# Sheet_4.net
KiCad netlist of a schematic drawn in Altium Designer
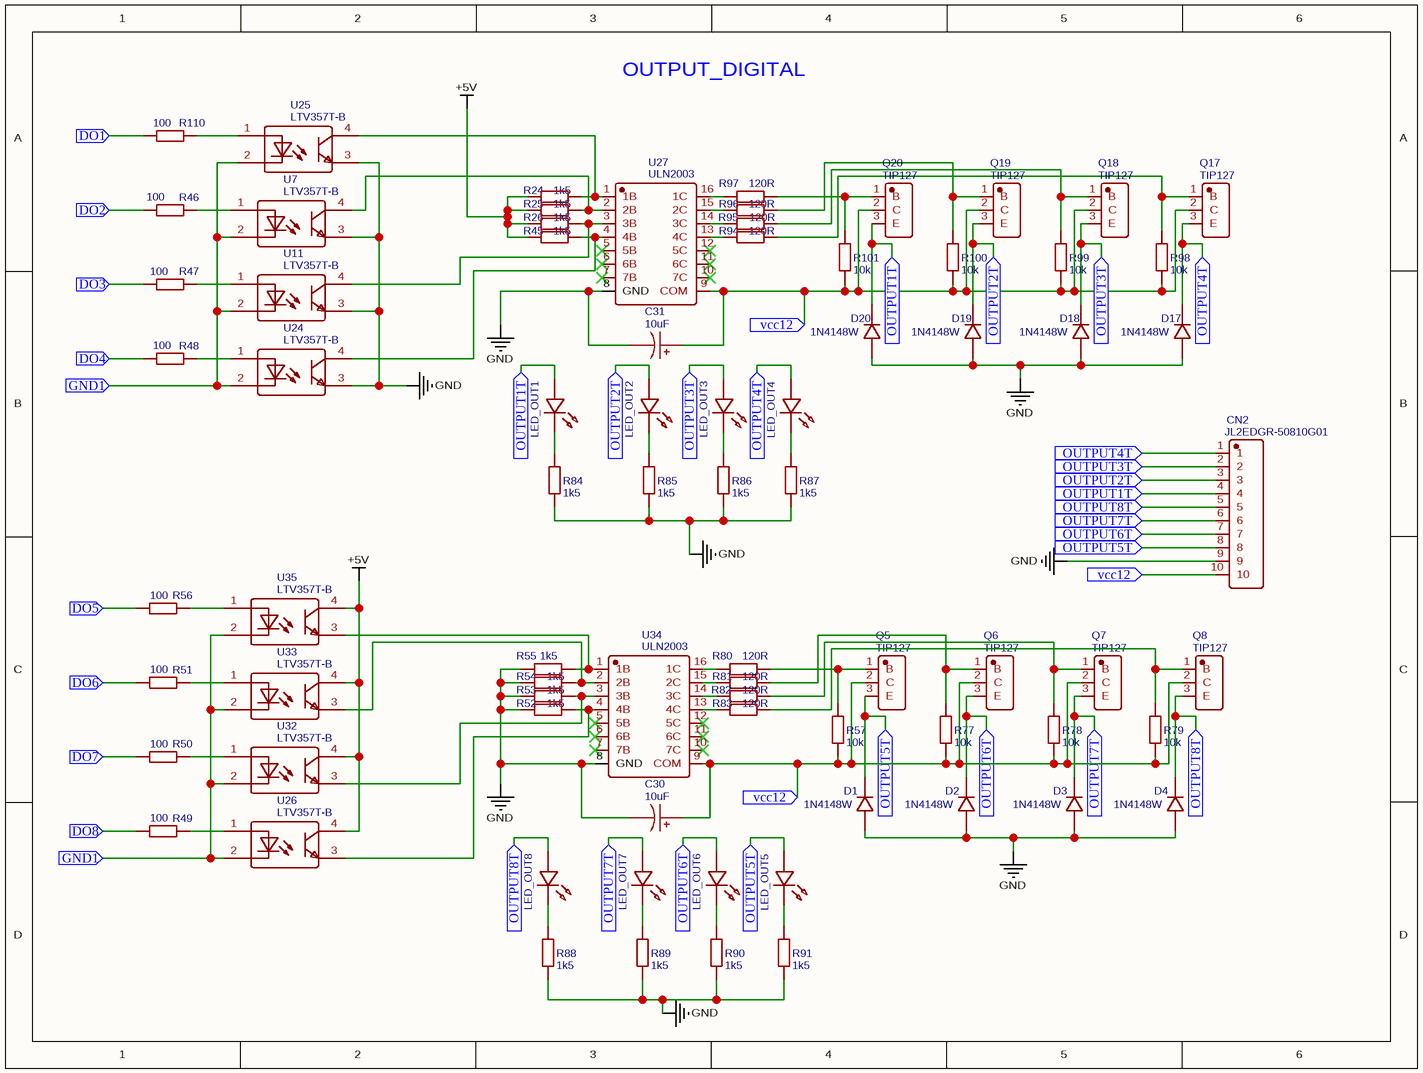
[diagram p0: Sheet_4.schdoc]

(export (version "E")
  (design (tool "Eeschema 10.0.6"))
  (components
    (comp (ref "C30")
      (value "10uF")
      (fields
        (field (name "BOM_SUPPLIER PART") "C503219")
        (field (name "BOM_MANUFACTURER PART") "01EC1809SHC10UF50V")
        (field (name "CONTRIBUTOR") "LCSC")
      )
      (libsource (lib "altium-import") (part "root_2_10uF_"))
    )
    (comp (ref "C31")
      (value "10uF")
      (fields
        (field (name "BOM_SUPPLIER PART") "C503219")
        (field (name "BOM_MANUFACTURER PART") "01EC1809SHC10UF50V")
        (field (name "CONTRIBUTOR") "LCSC")
      )
      (libsource (lib "altium-import") (part "root_2_10uF_"))
    )
    (comp (ref "CN2")
      (value "JL2EDGR-50810G01")
      (fields (field (name "BOM_SUPPLIER PART") "C424394") (field (name "CONTRIBUTOR") "LCSC"))
      (libsource (lib "altium-import") (part "root_0_JL2EDGR-50810G01_"))
    )
    (comp (ref "D1")
      (value "1N4148W")
      (fields (field (name "BOM_SUPPLIER PART") "C305437") (field (name "CONTRIBUTOR") "LCSC"))
      (libsource (lib "altium-import") (part "root_3_1N4148W_"))
    )
    (comp (ref "D2")
      (value "1N4148W")
      (fields (field (name "BOM_SUPPLIER PART") "C305437") (field (name "CONTRIBUTOR") "LCSC"))
      (libsource (lib "altium-import") (part "root_3_1N4148W_"))
    )
    (comp (ref "D3")
      (value "1N4148W")
      (fields (field (name "BOM_SUPPLIER PART") "C305437") (field (name "CONTRIBUTOR") "LCSC"))
      (libsource (lib "altium-import") (part "root_3_1N4148W_"))
    )
    (comp (ref "D4")
      (value "1N4148W")
      (fields (field (name "BOM_SUPPLIER PART") "C305437") (field (name "CONTRIBUTOR") "LCSC"))
      (libsource (lib "altium-import") (part "root_3_1N4148W_"))
    )
    (comp (ref "D17")
      (value "1N4148W")
      (fields (field (name "BOM_SUPPLIER PART") "C305437") (field (name "CONTRIBUTOR") "LCSC"))
      (libsource (lib "altium-import") (part "root_3_1N4148W_"))
    )
    (comp (ref "D18")
      (value "1N4148W")
      (fields (field (name "BOM_SUPPLIER PART") "C305437") (field (name "CONTRIBUTOR") "LCSC"))
      (libsource (lib "altium-import") (part "root_3_1N4148W_"))
    )
    (comp (ref "D19")
      (value "1N4148W")
      (fields (field (name "BOM_SUPPLIER PART") "C305437") (field (name "CONTRIBUTOR") "LCSC"))
      (libsource (lib "altium-import") (part "root_3_1N4148W_"))
    )
    (comp (ref "D20")
      (value "1N4148W")
      (fields (field (name "BOM_SUPPLIER PART") "C305437") (field (name "CONTRIBUTOR") "LCSC"))
      (libsource (lib "altium-import") (part "root_3_1N4148W_"))
    )
    (comp (ref "LED_OUT1")
      (value "red")
      (fields
        (field (name "BOM_SUPPLIER PART") "C568941")
        (field (name "BOM_MANUFACTURER PART") "HL-503H3GD")
        (field (name "CONTRIBUTOR") "LCSC")
      )
      (libsource (lib "altium-import") (part "root_3_red_"))
    )
    (comp (ref "LED_OUT2")
      (value "red")
      (fields
        (field (name "BOM_SUPPLIER PART") "C568941")
        (field (name "BOM_MANUFACTURER PART") "HL-503H3GD")
        (field (name "CONTRIBUTOR") "LCSC")
      )
      (libsource (lib "altium-import") (part "root_3_red_"))
    )
    (comp (ref "LED_OUT3")
      (value "red")
      (fields
        (field (name "BOM_SUPPLIER PART") "C568941")
        (field (name "BOM_MANUFACTURER PART") "HL-503H3GD")
        (field (name "CONTRIBUTOR") "LCSC")
      )
      (libsource (lib "altium-import") (part "root_3_red_"))
    )
    (comp (ref "LED_OUT4")
      (value "red")
      (fields
        (field (name "BOM_SUPPLIER PART") "C568941")
        (field (name "BOM_MANUFACTURER PART") "HL-503H3GD")
        (field (name "CONTRIBUTOR") "LCSC")
      )
      (libsource (lib "altium-import") (part "root_3_red_"))
    )
    (comp (ref "LED_OUT5")
      (value "red")
      (fields
        (field (name "BOM_SUPPLIER PART") "C568941")
        (field (name "BOM_MANUFACTURER PART") "HL-503H3GD")
        (field (name "CONTRIBUTOR") "LCSC")
      )
      (libsource (lib "altium-import") (part "root_3_red_"))
    )
    (comp (ref "LED_OUT6")
      (value "red")
      (fields
        (field (name "BOM_SUPPLIER PART") "C568941")
        (field (name "BOM_MANUFACTURER PART") "HL-503H3GD")
        (field (name "CONTRIBUTOR") "LCSC")
      )
      (libsource (lib "altium-import") (part "root_3_red_"))
    )
    (comp (ref "LED_OUT7")
      (value "red")
      (fields
        (field (name "BOM_SUPPLIER PART") "C568941")
        (field (name "BOM_MANUFACTURER PART") "HL-503H3GD")
        (field (name "CONTRIBUTOR") "LCSC")
      )
      (libsource (lib "altium-import") (part "root_3_red_"))
    )
    (comp (ref "LED_OUT8")
      (value "red")
      (fields
        (field (name "BOM_SUPPLIER PART") "C568941")
        (field (name "BOM_MANUFACTURER PART") "HL-503H3GD")
        (field (name "CONTRIBUTOR") "LCSC")
      )
      (libsource (lib "altium-import") (part "root_3_red_"))
    )
    (comp (ref "Q5")
      (value "TIP127")
      (fields (field (name "BOM_SUPPLIER PART") "C557885") (field (name "CONTRIBUTOR") "LCSC"))
      (libsource (lib "altium-import") (part "root_3_TIP127_"))
    )
    (comp (ref "Q6")
      (value "TIP127")
      (fields (field (name "BOM_SUPPLIER PART") "C557885") (field (name "CONTRIBUTOR") "LCSC"))
      (libsource (lib "altium-import") (part "root_3_TIP127_"))
    )
    (comp (ref "Q7")
      (value "TIP127")
      (fields (field (name "BOM_SUPPLIER PART") "C557885") (field (name "CONTRIBUTOR") "LCSC"))
      (libsource (lib "altium-import") (part "root_3_TIP127_"))
    )
    (comp (ref "Q8")
      (value "TIP127")
      (fields (field (name "BOM_SUPPLIER PART") "C557885") (field (name "CONTRIBUTOR") "LCSC"))
      (libsource (lib "altium-import") (part "root_3_TIP127_"))
    )
    (comp (ref "Q17")
      (value "TIP127")
      (fields (field (name "BOM_SUPPLIER PART") "C557885") (field (name "CONTRIBUTOR") "LCSC"))
      (libsource (lib "altium-import") (part "root_3_TIP127_"))
    )
    (comp (ref "Q18")
      (value "TIP127")
      (fields (field (name "BOM_SUPPLIER PART") "C557885") (field (name "CONTRIBUTOR") "LCSC"))
      (libsource (lib "altium-import") (part "root_3_TIP127_"))
    )
    (comp (ref "Q19")
      (value "TIP127")
      (fields (field (name "BOM_SUPPLIER PART") "C557885") (field (name "CONTRIBUTOR") "LCSC"))
      (libsource (lib "altium-import") (part "root_3_TIP127_"))
    )
    (comp (ref "Q20")
      (value "TIP127")
      (fields (field (name "BOM_SUPPLIER PART") "C557885") (field (name "CONTRIBUTOR") "LCSC"))
      (libsource (lib "altium-import") (part "root_3_TIP127_"))
    )
    (comp (ref "R24")
      (value "1k5")
      (fields (field (name "BOM_SUPPLIER PART") "C120038") (field (name "CONTRIBUTOR") "LCSC"))
      (libsource (lib "altium-import") (part "root_0_1k5_"))
    )
    (comp (ref "R25")
      (value "1k5")
      (fields (field (name "BOM_SUPPLIER PART") "C120038") (field (name "CONTRIBUTOR") "LCSC"))
      (libsource (lib "altium-import") (part "root_2_1k5_"))
    )
    (comp (ref "R26")
      (value "1k5")
      (fields (field (name "BOM_SUPPLIER PART") "C120038") (field (name "CONTRIBUTOR") "LCSC"))
      (libsource (lib "altium-import") (part "root_2_1k5_"))
    )
    (comp (ref "R45")
      (value "1k5")
      (fields (field (name "BOM_SUPPLIER PART") "C120038") (field (name "CONTRIBUTOR") "LCSC"))
      (libsource (lib "altium-import") (part "root_2_1k5_"))
    )
    (comp (ref "R46")
      (value "100")
      (fields (field (name "BOM_SUPPLIER PART") "C120038") (field (name "CONTRIBUTOR") "LCSC"))
      (libsource (lib "altium-import") (part "root_2_100_"))
    )
    (comp (ref "R47")
      (value "100")
      (fields (field (name "BOM_SUPPLIER PART") "C120038") (field (name "CONTRIBUTOR") "LCSC"))
      (libsource (lib "altium-import") (part "root_2_100_"))
    )
    (comp (ref "R48")
      (value "100")
      (fields (field (name "BOM_SUPPLIER PART") "C120038") (field (name "CONTRIBUTOR") "LCSC"))
      (libsource (lib "altium-import") (part "root_2_100_"))
    )
    (comp (ref "R49")
      (value "100")
      (fields (field (name "BOM_SUPPLIER PART") "C120038") (field (name "CONTRIBUTOR") "LCSC"))
      (libsource (lib "altium-import") (part "root_2_100_"))
    )
    (comp (ref "R50")
      (value "100")
      (fields (field (name "BOM_SUPPLIER PART") "C120038") (field (name "CONTRIBUTOR") "LCSC"))
      (libsource (lib "altium-import") (part "root_2_100_"))
    )
    (comp (ref "R51")
      (value "100")
      (fields (field (name "BOM_SUPPLIER PART") "C120038") (field (name "CONTRIBUTOR") "LCSC"))
      (libsource (lib "altium-import") (part "root_2_100_"))
    )
    (comp (ref "R52")
      (value "1k5")
      (fields (field (name "BOM_SUPPLIER PART") "C120038") (field (name "CONTRIBUTOR") "LCSC"))
      (libsource (lib "altium-import") (part "root_2_1k5_"))
    )
    (comp (ref "R53")
      (value "1k5")
      (fields (field (name "BOM_SUPPLIER PART") "C120038") (field (name "CONTRIBUTOR") "LCSC"))
      (libsource (lib "altium-import") (part "root_2_1k5_"))
    )
    (comp (ref "R54")
      (value "1k5")
      (fields (field (name "BOM_SUPPLIER PART") "C120038") (field (name "CONTRIBUTOR") "LCSC"))
      (libsource (lib "altium-import") (part "root_2_1k5_"))
    )
    (comp (ref "R55")
      (value "1k5")
      (fields (field (name "BOM_SUPPLIER PART") "C120038") (field (name "CONTRIBUTOR") "LCSC"))
      (libsource (lib "altium-import") (part "root_0_1k5_"))
    )
    (comp (ref "R56")
      (value "100")
      (fields (field (name "BOM_SUPPLIER PART") "C120038") (field (name "CONTRIBUTOR") "LCSC"))
      (libsource (lib "altium-import") (part "root_2_100_"))
    )
    (comp (ref "R57")
      (value "10k")
      (fields (field (name "BOM_SUPPLIER PART") "C120038") (field (name "CONTRIBUTOR") "LCSC"))
      (libsource (lib "altium-import") (part "root_3_10k_"))
    )
    (comp (ref "R77")
      (value "10k")
      (fields (field (name "BOM_SUPPLIER PART") "C120038") (field (name "CONTRIBUTOR") "LCSC"))
      (libsource (lib "altium-import") (part "root_3_10k_"))
    )
    (comp (ref "R78")
      (value "10k")
      (fields (field (name "BOM_SUPPLIER PART") "C120038") (field (name "CONTRIBUTOR") "LCSC"))
      (libsource (lib "altium-import") (part "root_3_10k_"))
    )
    (comp (ref "R79")
      (value "10k")
      (fields (field (name "BOM_SUPPLIER PART") "C120038") (field (name "CONTRIBUTOR") "LCSC"))
      (libsource (lib "altium-import") (part "root_3_10k_"))
    )
    (comp (ref "R80")
      (value "120R")
      (fields (field (name "BOM_SUPPLIER PART") "C120038") (field (name "CONTRIBUTOR") "LCSC"))
      (libsource (lib "altium-import") (part "root_2_120R_"))
    )
    (comp (ref "R81")
      (value "120R")
      (fields (field (name "BOM_SUPPLIER PART") "C120038") (field (name "CONTRIBUTOR") "LCSC"))
      (libsource (lib "altium-import") (part "root_2_120R_"))
    )
    (comp (ref "R82")
      (value "120R")
      (fields (field (name "BOM_SUPPLIER PART") "C120038") (field (name "CONTRIBUTOR") "LCSC"))
      (libsource (lib "altium-import") (part "root_2_120R_"))
    )
    (comp (ref "R83")
      (value "120R")
      (fields (field (name "BOM_SUPPLIER PART") "C120038") (field (name "CONTRIBUTOR") "LCSC"))
      (libsource (lib "altium-import") (part "root_2_120R_"))
    )
    (comp (ref "R84")
      (value "1k5")
      (fields (field (name "BOM_SUPPLIER PART") "C120038") (field (name "CONTRIBUTOR") "LCSC"))
      (libsource (lib "altium-import") (part "root_3_1k5_"))
    )
    (comp (ref "R85")
      (value "1k5")
      (fields (field (name "BOM_SUPPLIER PART") "C120038") (field (name "CONTRIBUTOR") "LCSC"))
      (libsource (lib "altium-import") (part "root_3_1k5_"))
    )
    (comp (ref "R86")
      (value "1k5")
      (fields (field (name "BOM_SUPPLIER PART") "C120038") (field (name "CONTRIBUTOR") "LCSC"))
      (libsource (lib "altium-import") (part "root_3_1k5_"))
    )
    (comp (ref "R87")
      (value "1k5")
      (fields (field (name "BOM_SUPPLIER PART") "C120038") (field (name "CONTRIBUTOR") "LCSC"))
      (libsource (lib "altium-import") (part "root_3_1k5_"))
    )
    (comp (ref "R88")
      (value "1k5")
      (fields (field (name "BOM_SUPPLIER PART") "C120038") (field (name "CONTRIBUTOR") "LCSC"))
      (libsource (lib "altium-import") (part "root_3_1k5_"))
    )
    (comp (ref "R89")
      (value "1k5")
      (fields (field (name "BOM_SUPPLIER PART") "C120038") (field (name "CONTRIBUTOR") "LCSC"))
      (libsource (lib "altium-import") (part "root_3_1k5_"))
    )
    (comp (ref "R90")
      (value "1k5")
      (fields (field (name "BOM_SUPPLIER PART") "C120038") (field (name "CONTRIBUTOR") "LCSC"))
      (libsource (lib "altium-import") (part "root_3_1k5_"))
    )
    (comp (ref "R91")
      (value "1k5")
      (fields (field (name "BOM_SUPPLIER PART") "C120038") (field (name "CONTRIBUTOR") "LCSC"))
      (libsource (lib "altium-import") (part "root_3_1k5_"))
    )
    (comp (ref "R94")
      (value "120R")
      (fields (field (name "BOM_SUPPLIER PART") "C120038") (field (name "CONTRIBUTOR") "LCSC"))
      (libsource (lib "altium-import") (part "root_2_120R_"))
    )
    (comp (ref "R95")
      (value "120R")
      (fields (field (name "BOM_SUPPLIER PART") "C120038") (field (name "CONTRIBUTOR") "LCSC"))
      (libsource (lib "altium-import") (part "root_2_120R_"))
    )
    (comp (ref "R96")
      (value "120R")
      (fields (field (name "BOM_SUPPLIER PART") "C120038") (field (name "CONTRIBUTOR") "LCSC"))
      (libsource (lib "altium-import") (part "root_2_120R_"))
    )
    (comp (ref "R97")
      (value "120R")
      (fields (field (name "BOM_SUPPLIER PART") "C120038") (field (name "CONTRIBUTOR") "LCSC"))
      (libsource (lib "altium-import") (part "root_2_120R_"))
    )
    (comp (ref "R98")
      (value "10k")
      (fields (field (name "BOM_SUPPLIER PART") "C120038") (field (name "CONTRIBUTOR") "LCSC"))
      (libsource (lib "altium-import") (part "root_3_10k_"))
    )
    (comp (ref "R99")
      (value "10k")
      (fields (field (name "BOM_SUPPLIER PART") "C120038") (field (name "CONTRIBUTOR") "LCSC"))
      (libsource (lib "altium-import") (part "root_3_10k_"))
    )
    (comp (ref "R100")
      (value "10k")
      (fields (field (name "BOM_SUPPLIER PART") "C120038") (field (name "CONTRIBUTOR") "LCSC"))
      (libsource (lib "altium-import") (part "root_3_10k_"))
    )
    (comp (ref "R101")
      (value "10k")
      (fields (field (name "BOM_SUPPLIER PART") "C120038") (field (name "CONTRIBUTOR") "LCSC"))
      (libsource (lib "altium-import") (part "root_3_10k_"))
    )
    (comp (ref "R110")
      (value "100")
      (fields (field (name "BOM_SUPPLIER PART") "C120038") (field (name "CONTRIBUTOR") "LCSC"))
      (libsource (lib "altium-import") (part "root_2_100_"))
    )
    (comp (ref "U7")
      (value "LTV357T-B")
      (fields (field (name "BOM_SUPPLIER PART") "C33068") (field (name "CONTRIBUTOR") "LCSC"))
      (libsource (lib "altium-import") (part "root_0_LTV357T-B_"))
    )
    (comp (ref "U11")
      (value "LTV357T-B")
      (fields (field (name "BOM_SUPPLIER PART") "C33068") (field (name "CONTRIBUTOR") "LCSC"))
      (libsource (lib "altium-import") (part "root_0_LTV357T-B_"))
    )
    (comp (ref "U24")
      (value "LTV357T-B")
      (fields (field (name "BOM_SUPPLIER PART") "C33068") (field (name "CONTRIBUTOR") "LCSC"))
      (libsource (lib "altium-import") (part "root_0_LTV357T-B_"))
    )
    (comp (ref "U25")
      (value "LTV357T-B")
      (fields (field (name "BOM_SUPPLIER PART") "C33068") (field (name "CONTRIBUTOR") "LCSC"))
      (libsource (lib "altium-import") (part "root_0_LTV357T-B_"))
    )
    (comp (ref "U26")
      (value "LTV357T-B")
      (fields (field (name "BOM_SUPPLIER PART") "C33068") (field (name "CONTRIBUTOR") "LCSC"))
      (libsource (lib "altium-import") (part "root_0_LTV357T-B_"))
    )
    (comp (ref "U27")
      (value "ULN2003")
      (fields (field (name "BOM_SUPPLIER PART") "C2829422") (field (name "CONTRIBUTOR") "LCSC"))
      (libsource (lib "altium-import") (part "root_0_ULN2003_"))
    )
    (comp (ref "U32")
      (value "LTV357T-B")
      (fields (field (name "BOM_SUPPLIER PART") "C33068") (field (name "CONTRIBUTOR") "LCSC"))
      (libsource (lib "altium-import") (part "root_0_LTV357T-B_"))
    )
    (comp (ref "U33")
      (value "LTV357T-B")
      (fields (field (name "BOM_SUPPLIER PART") "C33068") (field (name "CONTRIBUTOR") "LCSC"))
      (libsource (lib "altium-import") (part "root_0_LTV357T-B_"))
    )
    (comp (ref "U34")
      (value "ULN2003")
      (fields (field (name "BOM_SUPPLIER PART") "C2829422") (field (name "CONTRIBUTOR") "LCSC"))
      (libsource (lib "altium-import") (part "root_0_ULN2003_"))
    )
    (comp (ref "U35")
      (value "LTV357T-B")
      (fields (field (name "BOM_SUPPLIER PART") "C33068") (field (name "CONTRIBUTOR") "LCSC"))
      (libsource (lib "altium-import") (part "root_0_LTV357T-B_"))
    )
  )
  (nets
    (net (code "1") (name "+5V") (class "Default")
      (node (ref "R24") (pin "1") (pinfunction "1_1") (pintype "passive"))
      (node (ref "R25") (pin "2") (pinfunction "2_2") (pintype "passive"))
      (node (ref "R26") (pin "2") (pinfunction "2_2") (pintype "passive"))
      (node (ref "R45") (pin "2") (pinfunction "2_2") (pintype "passive"))
      (node (ref "U26") (pin "4") (pinfunction "4_4") (pintype "passive"))
      (node (ref "U32") (pin "4") (pinfunction "4_4") (pintype "passive"))
      (node (ref "U33") (pin "4") (pinfunction "4_4") (pintype "passive"))
      (node (ref "U35") (pin "4") (pinfunction "4_4") (pintype "passive"))
    )
    (net (code "2") (name "/DO1") (class "Default")
      (node (ref "R110") (pin "2") (pinfunction "2_2") (pintype "passive"))
    )
    (net (code "3") (name "/DO2") (class "Default")
      (node (ref "R46") (pin "2") (pinfunction "2_2") (pintype "passive"))
    )
    (net (code "4") (name "/DO3") (class "Default")
      (node (ref "R47") (pin "2") (pinfunction "2_2") (pintype "passive"))
    )
    (net (code "5") (name "/DO4") (class "Default")
      (node (ref "R48") (pin "2") (pinfunction "2_2") (pintype "passive"))
    )
    (net (code "6") (name "/DO5") (class "Default")
      (node (ref "R56") (pin "2") (pinfunction "2_2") (pintype "passive"))
    )
    (net (code "7") (name "/DO6") (class "Default")
      (node (ref "R51") (pin "2") (pinfunction "2_2") (pintype "passive"))
    )
    (net (code "8") (name "/DO7") (class "Default")
      (node (ref "R50") (pin "2") (pinfunction "2_2") (pintype "passive"))
    )
    (net (code "9") (name "/DO8") (class "Default")
      (node (ref "R49") (pin "2") (pinfunction "2_2") (pintype "passive"))
    )
    (net (code "10") (name "/GND1") (class "Default")
      (node (ref "U11") (pin "2") (pinfunction "2_2") (pintype "passive"))
      (node (ref "U24") (pin "2") (pinfunction "2_2") (pintype "passive"))
      (node (ref "U25") (pin "2") (pinfunction "2_2") (pintype "passive"))
      (node (ref "U26") (pin "2") (pinfunction "2_2") (pintype "passive"))
      (node (ref "U32") (pin "2") (pinfunction "2_2") (pintype "passive"))
      (node (ref "U33") (pin "2") (pinfunction "2_2") (pintype "passive"))
      (node (ref "U35") (pin "2") (pinfunction "2_2") (pintype "passive"))
      (node (ref "U7") (pin "2") (pinfunction "2_2") (pintype "passive"))
    )
    (net (code "11") (name "/OUTPUT1T") (class "Default")
      (node (ref "CN2") (pin "4") (pinfunction "4_4") (pintype "passive"))
      (node (ref "D20") (pin "1") (pinfunction "1_1") (pintype "passive"))
      (node (ref "LED_OUT1") (pin "1") (pinfunction "1_1") (pintype "passive"))
      (node (ref "Q20") (pin "3") (pinfunction "E_3") (pintype "passive"))
    )
    (net (code "12") (name "/OUTPUT2T") (class "Default")
      (node (ref "CN2") (pin "3") (pinfunction "3_3") (pintype "passive"))
      (node (ref "D19") (pin "1") (pinfunction "1_1") (pintype "passive"))
      (node (ref "LED_OUT2") (pin "1") (pinfunction "1_1") (pintype "passive"))
      (node (ref "Q19") (pin "3") (pinfunction "E_3") (pintype "passive"))
    )
    (net (code "13") (name "/OUTPUT3T") (class "Default")
      (node (ref "CN2") (pin "2") (pinfunction "2_2") (pintype "passive"))
      (node (ref "D18") (pin "1") (pinfunction "1_1") (pintype "passive"))
      (node (ref "LED_OUT3") (pin "1") (pinfunction "1_1") (pintype "passive"))
      (node (ref "Q18") (pin "3") (pinfunction "E_3") (pintype "passive"))
    )
    (net (code "14") (name "/OUTPUT4T") (class "Default")
      (node (ref "CN2") (pin "1") (pinfunction "1_1") (pintype "passive"))
      (node (ref "D17") (pin "1") (pinfunction "1_1") (pintype "passive"))
      (node (ref "LED_OUT4") (pin "1") (pinfunction "1_1") (pintype "passive"))
      (node (ref "Q17") (pin "3") (pinfunction "E_3") (pintype "passive"))
    )
    (net (code "15") (name "/OUTPUT5T") (class "Default")
      (node (ref "CN2") (pin "8") (pinfunction "8_8") (pintype "passive"))
      (node (ref "D1") (pin "1") (pinfunction "1_1") (pintype "passive"))
      (node (ref "LED_OUT5") (pin "1") (pinfunction "1_1") (pintype "passive"))
      (node (ref "Q5") (pin "3") (pinfunction "E_3") (pintype "passive"))
    )
    (net (code "16") (name "/OUTPUT6T") (class "Default")
      (node (ref "CN2") (pin "7") (pinfunction "7_7") (pintype "passive"))
      (node (ref "D2") (pin "1") (pinfunction "1_1") (pintype "passive"))
      (node (ref "LED_OUT6") (pin "1") (pinfunction "1_1") (pintype "passive"))
      (node (ref "Q6") (pin "3") (pinfunction "E_3") (pintype "passive"))
    )
    (net (code "17") (name "/OUTPUT7T") (class "Default")
      (node (ref "CN2") (pin "6") (pinfunction "6_6") (pintype "passive"))
      (node (ref "D3") (pin "1") (pinfunction "1_1") (pintype "passive"))
      (node (ref "LED_OUT7") (pin "1") (pinfunction "1_1") (pintype "passive"))
      (node (ref "Q7") (pin "3") (pinfunction "E_3") (pintype "passive"))
    )
    (net (code "18") (name "/OUTPUT8T") (class "Default")
      (node (ref "CN2") (pin "5") (pinfunction "5_5") (pintype "passive"))
      (node (ref "D4") (pin "1") (pinfunction "1_1") (pintype "passive"))
      (node (ref "LED_OUT8") (pin "1") (pinfunction "1_1") (pintype "passive"))
      (node (ref "Q8") (pin "3") (pinfunction "E_3") (pintype "passive"))
    )
    (net (code "19") (name "/vcc12") (class "Default")
      (node (ref "C30") (pin "1") (pinfunction "1_1") (pintype "passive"))
      (node (ref "C31") (pin "1") (pinfunction "1_1") (pintype "passive"))
      (node (ref "CN2") (pin "10") (pinfunction "10_10") (pintype "passive"))
      (node (ref "Q17") (pin "2") (pinfunction "C_2") (pintype "passive"))
      (node (ref "Q18") (pin "2") (pinfunction "C_2") (pintype "passive"))
      (node (ref "Q19") (pin "2") (pinfunction "C_2") (pintype "passive"))
      (node (ref "Q20") (pin "2") (pinfunction "C_2") (pintype "passive"))
      (node (ref "Q5") (pin "2") (pinfunction "C_2") (pintype "passive"))
      (node (ref "Q6") (pin "2") (pinfunction "C_2") (pintype "passive"))
      (node (ref "Q7") (pin "2") (pinfunction "C_2") (pintype "passive"))
      (node (ref "Q8") (pin "2") (pinfunction "C_2") (pintype "passive"))
      (node (ref "R100") (pin "2") (pinfunction "2_2") (pintype "passive"))
      (node (ref "R101") (pin "2") (pinfunction "2_2") (pintype "passive"))
      (node (ref "R57") (pin "2") (pinfunction "2_2") (pintype "passive"))
      (node (ref "R77") (pin "2") (pinfunction "2_2") (pintype "passive"))
      (node (ref "R78") (pin "2") (pinfunction "2_2") (pintype "passive"))
      (node (ref "R79") (pin "2") (pinfunction "2_2") (pintype "passive"))
      (node (ref "R98") (pin "2") (pinfunction "2_2") (pintype "passive"))
      (node (ref "R99") (pin "2") (pinfunction "2_2") (pintype "passive"))
      (node (ref "U27") (pin "9") (pinfunction "COM_9") (pintype "passive"))
      (node (ref "U34") (pin "9") (pinfunction "COM_9") (pintype "passive"))
    )
    (net (code "20") (name "GND") (class "Default")
      (node (ref "C30") (pin "2") (pinfunction "2_2") (pintype "passive"))
      (node (ref "C31") (pin "2") (pinfunction "2_2") (pintype "passive"))
      (node (ref "CN2") (pin "9") (pinfunction "9_9") (pintype "passive"))
      (node (ref "D1") (pin "2") (pinfunction "2_2") (pintype "passive"))
      (node (ref "D17") (pin "2") (pinfunction "2_2") (pintype "passive"))
      (node (ref "D18") (pin "2") (pinfunction "2_2") (pintype "passive"))
      (node (ref "D19") (pin "2") (pinfunction "2_2") (pintype "passive"))
      (node (ref "D2") (pin "2") (pinfunction "2_2") (pintype "passive"))
      (node (ref "D20") (pin "2") (pinfunction "2_2") (pintype "passive"))
      (node (ref "D3") (pin "2") (pinfunction "2_2") (pintype "passive"))
      (node (ref "D4") (pin "2") (pinfunction "2_2") (pintype "passive"))
      (node (ref "R52") (pin "2") (pinfunction "2_2") (pintype "passive"))
      (node (ref "R53") (pin "2") (pinfunction "2_2") (pintype "passive"))
      (node (ref "R54") (pin "2") (pinfunction "2_2") (pintype "passive"))
      (node (ref "R55") (pin "1") (pinfunction "1_1") (pintype "passive"))
      (node (ref "R84") (pin "2") (pinfunction "2_2") (pintype "passive"))
      (node (ref "R85") (pin "2") (pinfunction "2_2") (pintype "passive"))
      (node (ref "R86") (pin "2") (pinfunction "2_2") (pintype "passive"))
      (node (ref "R87") (pin "2") (pinfunction "2_2") (pintype "passive"))
      (node (ref "R88") (pin "2") (pinfunction "2_2") (pintype "passive"))
      (node (ref "R89") (pin "2") (pinfunction "2_2") (pintype "passive"))
      (node (ref "R90") (pin "2") (pinfunction "2_2") (pintype "passive"))
      (node (ref "R91") (pin "2") (pinfunction "2_2") (pintype "passive"))
      (node (ref "U11") (pin "3") (pinfunction "3_3") (pintype "passive"))
      (node (ref "U24") (pin "3") (pinfunction "3_3") (pintype "passive"))
      (node (ref "U25") (pin "3") (pinfunction "3_3") (pintype "passive"))
      (node (ref "U27") (pin "8") (pinfunction "GND_8") (pintype "passive"))
      (node (ref "U34") (pin "8") (pinfunction "GND_8") (pintype "passive"))
      (node (ref "U7") (pin "3") (pinfunction "3_3") (pintype "passive"))
    )
    (net (code "21") (name "Net-(LED_OUT1-Pad2)") (class "Default")
      (node (ref "LED_OUT1") (pin "2") (pinfunction "2_2") (pintype "passive"))
      (node (ref "R84") (pin "1") (pinfunction "1_1") (pintype "passive"))
    )
    (net (code "22") (name "Net-(LED_OUT2-Pad2)") (class "Default")
      (node (ref "LED_OUT2") (pin "2") (pinfunction "2_2") (pintype "passive"))
      (node (ref "R85") (pin "1") (pinfunction "1_1") (pintype "passive"))
    )
    (net (code "23") (name "Net-(LED_OUT3-Pad2)") (class "Default")
      (node (ref "LED_OUT3") (pin "2") (pinfunction "2_2") (pintype "passive"))
      (node (ref "R86") (pin "1") (pinfunction "1_1") (pintype "passive"))
    )
    (net (code "24") (name "Net-(LED_OUT4-Pad2)") (class "Default")
      (node (ref "LED_OUT4") (pin "2") (pinfunction "2_2") (pintype "passive"))
      (node (ref "R87") (pin "1") (pinfunction "1_1") (pintype "passive"))
    )
    (net (code "25") (name "Net-(LED_OUT5-Pad2)") (class "Default")
      (node (ref "LED_OUT5") (pin "2") (pinfunction "2_2") (pintype "passive"))
      (node (ref "R91") (pin "1") (pinfunction "1_1") (pintype "passive"))
    )
    (net (code "26") (name "Net-(LED_OUT6-Pad2)") (class "Default")
      (node (ref "LED_OUT6") (pin "2") (pinfunction "2_2") (pintype "passive"))
      (node (ref "R90") (pin "1") (pinfunction "1_1") (pintype "passive"))
    )
    (net (code "27") (name "Net-(LED_OUT7-Pad2)") (class "Default")
      (node (ref "LED_OUT7") (pin "2") (pinfunction "2_2") (pintype "passive"))
      (node (ref "R89") (pin "1") (pinfunction "1_1") (pintype "passive"))
    )
    (net (code "28") (name "Net-(LED_OUT8-Pad2)") (class "Default")
      (node (ref "LED_OUT8") (pin "2") (pinfunction "2_2") (pintype "passive"))
      (node (ref "R88") (pin "1") (pinfunction "1_1") (pintype "passive"))
    )
    (net (code "29") (name "Net-(Q5-B)") (class "Default")
      (node (ref "Q5") (pin "1") (pinfunction "B_1") (pintype "passive"))
      (node (ref "R57") (pin "1") (pinfunction "1_1") (pintype "passive"))
      (node (ref "R80") (pin "1") (pinfunction "1_1") (pintype "passive"))
    )
    (net (code "30") (name "Net-(Q6-B)") (class "Default")
      (node (ref "Q6") (pin "1") (pinfunction "B_1") (pintype "passive"))
      (node (ref "R77") (pin "1") (pinfunction "1_1") (pintype "passive"))
      (node (ref "R81") (pin "1") (pinfunction "1_1") (pintype "passive"))
    )
    (net (code "31") (name "Net-(Q7-B)") (class "Default")
      (node (ref "Q7") (pin "1") (pinfunction "B_1") (pintype "passive"))
      (node (ref "R78") (pin "1") (pinfunction "1_1") (pintype "passive"))
      (node (ref "R82") (pin "1") (pinfunction "1_1") (pintype "passive"))
    )
    (net (code "32") (name "Net-(Q8-B)") (class "Default")
      (node (ref "Q8") (pin "1") (pinfunction "B_1") (pintype "passive"))
      (node (ref "R79") (pin "1") (pinfunction "1_1") (pintype "passive"))
      (node (ref "R83") (pin "1") (pinfunction "1_1") (pintype "passive"))
    )
    (net (code "33") (name "Net-(Q17-B)") (class "Default")
      (node (ref "Q17") (pin "1") (pinfunction "B_1") (pintype "passive"))
      (node (ref "R94") (pin "1") (pinfunction "1_1") (pintype "passive"))
      (node (ref "R98") (pin "1") (pinfunction "1_1") (pintype "passive"))
    )
    (net (code "34") (name "Net-(Q18-B)") (class "Default")
      (node (ref "Q18") (pin "1") (pinfunction "B_1") (pintype "passive"))
      (node (ref "R95") (pin "1") (pinfunction "1_1") (pintype "passive"))
      (node (ref "R99") (pin "1") (pinfunction "1_1") (pintype "passive"))
    )
    (net (code "35") (name "Net-(Q19-B)") (class "Default")
      (node (ref "Q19") (pin "1") (pinfunction "B_1") (pintype "passive"))
      (node (ref "R100") (pin "1") (pinfunction "1_1") (pintype "passive"))
      (node (ref "R96") (pin "1") (pinfunction "1_1") (pintype "passive"))
    )
    (net (code "36") (name "Net-(Q20-B)") (class "Default")
      (node (ref "Q20") (pin "1") (pinfunction "B_1") (pintype "passive"))
      (node (ref "R101") (pin "1") (pinfunction "1_1") (pintype "passive"))
      (node (ref "R97") (pin "1") (pinfunction "1_1") (pintype "passive"))
    )
    (net (code "37") (name "Net-(R46-Pad1)") (class "Default")
      (node (ref "R46") (pin "1") (pinfunction "1_1") (pintype "passive"))
      (node (ref "U7") (pin "1") (pinfunction "1_1") (pintype "passive"))
    )
    (net (code "38") (name "Net-(R47-Pad1)") (class "Default")
      (node (ref "R47") (pin "1") (pinfunction "1_1") (pintype "passive"))
      (node (ref "U11") (pin "1") (pinfunction "1_1") (pintype "passive"))
    )
    (net (code "39") (name "Net-(R48-Pad1)") (class "Default")
      (node (ref "R48") (pin "1") (pinfunction "1_1") (pintype "passive"))
      (node (ref "U24") (pin "1") (pinfunction "1_1") (pintype "passive"))
    )
    (net (code "40") (name "Net-(R49-Pad1)") (class "Default")
      (node (ref "R49") (pin "1") (pinfunction "1_1") (pintype "passive"))
      (node (ref "U26") (pin "1") (pinfunction "1_1") (pintype "passive"))
    )
    (net (code "41") (name "Net-(R50-Pad1)") (class "Default")
      (node (ref "R50") (pin "1") (pinfunction "1_1") (pintype "passive"))
      (node (ref "U32") (pin "1") (pinfunction "1_1") (pintype "passive"))
    )
    (net (code "42") (name "Net-(R51-Pad1)") (class "Default")
      (node (ref "R51") (pin "1") (pinfunction "1_1") (pintype "passive"))
      (node (ref "U33") (pin "1") (pinfunction "1_1") (pintype "passive"))
    )
    (net (code "43") (name "Net-(R56-Pad1)") (class "Default")
      (node (ref "R56") (pin "1") (pinfunction "1_1") (pintype "passive"))
      (node (ref "U35") (pin "1") (pinfunction "1_1") (pintype "passive"))
    )
    (net (code "44") (name "Net-(R110-Pad1)") (class "Default")
      (node (ref "R110") (pin "1") (pinfunction "1_1") (pintype "passive"))
      (node (ref "U25") (pin "1") (pinfunction "1_1") (pintype "passive"))
    )
    (net (code "45") (name "Net-(U27-1B)") (class "Default")
      (node (ref "R24") (pin "2") (pinfunction "2_2") (pintype "passive"))
      (node (ref "U25") (pin "4") (pinfunction "4_4") (pintype "passive"))
      (node (ref "U27") (pin "1") (pinfunction "1B_1") (pintype "passive"))
    )
    (net (code "46") (name "Net-(U27-1C)") (class "Default")
      (node (ref "R97") (pin "2") (pinfunction "2_2") (pintype "passive"))
      (node (ref "U27") (pin "16") (pinfunction "1C_16") (pintype "passive"))
    )
    (net (code "47") (name "Net-(U27-2B)") (class "Default")
      (node (ref "R25") (pin "1") (pinfunction "1_1") (pintype "passive"))
      (node (ref "U27") (pin "2") (pinfunction "2B_2") (pintype "passive"))
      (node (ref "U7") (pin "4") (pinfunction "4_4") (pintype "passive"))
    )
    (net (code "48") (name "Net-(U27-2C)") (class "Default")
      (node (ref "R96") (pin "2") (pinfunction "2_2") (pintype "passive"))
      (node (ref "U27") (pin "15") (pinfunction "2C_15") (pintype "passive"))
    )
    (net (code "49") (name "Net-(U27-3B)") (class "Default")
      (node (ref "R26") (pin "1") (pinfunction "1_1") (pintype "passive"))
      (node (ref "U11") (pin "4") (pinfunction "4_4") (pintype "passive"))
      (node (ref "U27") (pin "3") (pinfunction "3B_3") (pintype "passive"))
    )
    (net (code "50") (name "Net-(U27-3C)") (class "Default")
      (node (ref "R95") (pin "2") (pinfunction "2_2") (pintype "passive"))
      (node (ref "U27") (pin "14") (pinfunction "3C_14") (pintype "passive"))
    )
    (net (code "51") (name "Net-(U27-4B)") (class "Default")
      (node (ref "R45") (pin "1") (pinfunction "1_1") (pintype "passive"))
      (node (ref "U24") (pin "4") (pinfunction "4_4") (pintype "passive"))
      (node (ref "U27") (pin "4") (pinfunction "4B_4") (pintype "passive"))
    )
    (net (code "52") (name "Net-(U27-4C)") (class "Default")
      (node (ref "R94") (pin "2") (pinfunction "2_2") (pintype "passive"))
      (node (ref "U27") (pin "13") (pinfunction "4C_13") (pintype "passive"))
    )
    (net (code "53") (name "Net-(U34-1B)") (class "Default")
      (node (ref "R55") (pin "2") (pinfunction "2_2") (pintype "passive"))
      (node (ref "U34") (pin "1") (pinfunction "1B_1") (pintype "passive"))
      (node (ref "U35") (pin "3") (pinfunction "3_3") (pintype "passive"))
    )
    (net (code "54") (name "Net-(U34-1C)") (class "Default")
      (node (ref "R80") (pin "2") (pinfunction "2_2") (pintype "passive"))
      (node (ref "U34") (pin "16") (pinfunction "1C_16") (pintype "passive"))
    )
    (net (code "55") (name "Net-(U34-2B)") (class "Default")
      (node (ref "R54") (pin "1") (pinfunction "1_1") (pintype "passive"))
      (node (ref "U33") (pin "3") (pinfunction "3_3") (pintype "passive"))
      (node (ref "U34") (pin "2") (pinfunction "2B_2") (pintype "passive"))
    )
    (net (code "56") (name "Net-(U34-2C)") (class "Default")
      (node (ref "R81") (pin "2") (pinfunction "2_2") (pintype "passive"))
      (node (ref "U34") (pin "15") (pinfunction "2C_15") (pintype "passive"))
    )
    (net (code "57") (name "Net-(U34-3B)") (class "Default")
      (node (ref "R53") (pin "1") (pinfunction "1_1") (pintype "passive"))
      (node (ref "U32") (pin "3") (pinfunction "3_3") (pintype "passive"))
      (node (ref "U34") (pin "3") (pinfunction "3B_3") (pintype "passive"))
    )
    (net (code "58") (name "Net-(U34-3C)") (class "Default")
      (node (ref "R82") (pin "2") (pinfunction "2_2") (pintype "passive"))
      (node (ref "U34") (pin "14") (pinfunction "3C_14") (pintype "passive"))
    )
    (net (code "59") (name "Net-(U34-4B)") (class "Default")
      (node (ref "R52") (pin "1") (pinfunction "1_1") (pintype "passive"))
      (node (ref "U26") (pin "3") (pinfunction "3_3") (pintype "passive"))
      (node (ref "U34") (pin "4") (pinfunction "4B_4") (pintype "passive"))
    )
    (net (code "60") (name "Net-(U34-4C)") (class "Default")
      (node (ref "R83") (pin "2") (pinfunction "2_2") (pintype "passive"))
      (node (ref "U34") (pin "13") (pinfunction "4C_13") (pintype "passive"))
    )
    (net (code "61") (name "unconnected-(U27-5B-Pad5)") (class "Default")
      (node (ref "U27") (pin "5") (pinfunction "5B_5") (pintype "passive+no_connect"))
    )
    (net (code "62") (name "unconnected-(U27-5C-Pad12)") (class "Default")
      (node (ref "U27") (pin "12") (pinfunction "5C_12") (pintype "passive+no_connect"))
    )
    (net (code "63") (name "unconnected-(U27-6B-Pad6)") (class "Default")
      (node (ref "U27") (pin "6") (pinfunction "6B_6") (pintype "passive+no_connect"))
    )
    (net (code "64") (name "unconnected-(U27-6C-Pad11)") (class "Default")
      (node (ref "U27") (pin "11") (pinfunction "6C_11") (pintype "passive+no_connect"))
    )
    (net (code "65") (name "unconnected-(U27-7B-Pad7)") (class "Default")
      (node (ref "U27") (pin "7") (pinfunction "7B_7") (pintype "passive+no_connect"))
    )
    (net (code "66") (name "unconnected-(U27-7C-Pad10)") (class "Default")
      (node (ref "U27") (pin "10") (pinfunction "7C_10") (pintype "passive+no_connect"))
    )
    (net (code "67") (name "unconnected-(U34-5B-Pad5)") (class "Default")
      (node (ref "U34") (pin "5") (pinfunction "5B_5") (pintype "passive+no_connect"))
    )
    (net (code "68") (name "unconnected-(U34-5C-Pad12)") (class "Default")
      (node (ref "U34") (pin "12") (pinfunction "5C_12") (pintype "passive+no_connect"))
    )
    (net (code "69") (name "unconnected-(U34-6B-Pad6)") (class "Default")
      (node (ref "U34") (pin "6") (pinfunction "6B_6") (pintype "passive+no_connect"))
    )
    (net (code "70") (name "unconnected-(U34-6C-Pad11)") (class "Default")
      (node (ref "U34") (pin "11") (pinfunction "6C_11") (pintype "passive+no_connect"))
    )
    (net (code "71") (name "unconnected-(U34-7B-Pad7)") (class "Default")
      (node (ref "U34") (pin "7") (pinfunction "7B_7") (pintype "passive+no_connect"))
    )
    (net (code "72") (name "unconnected-(U34-7C-Pad10)") (class "Default")
      (node (ref "U34") (pin "10") (pinfunction "7C_10") (pintype "passive+no_connect"))
    )
  )
)
